# design.net
KiCad netlist of a schematic drawn in Altium Designer
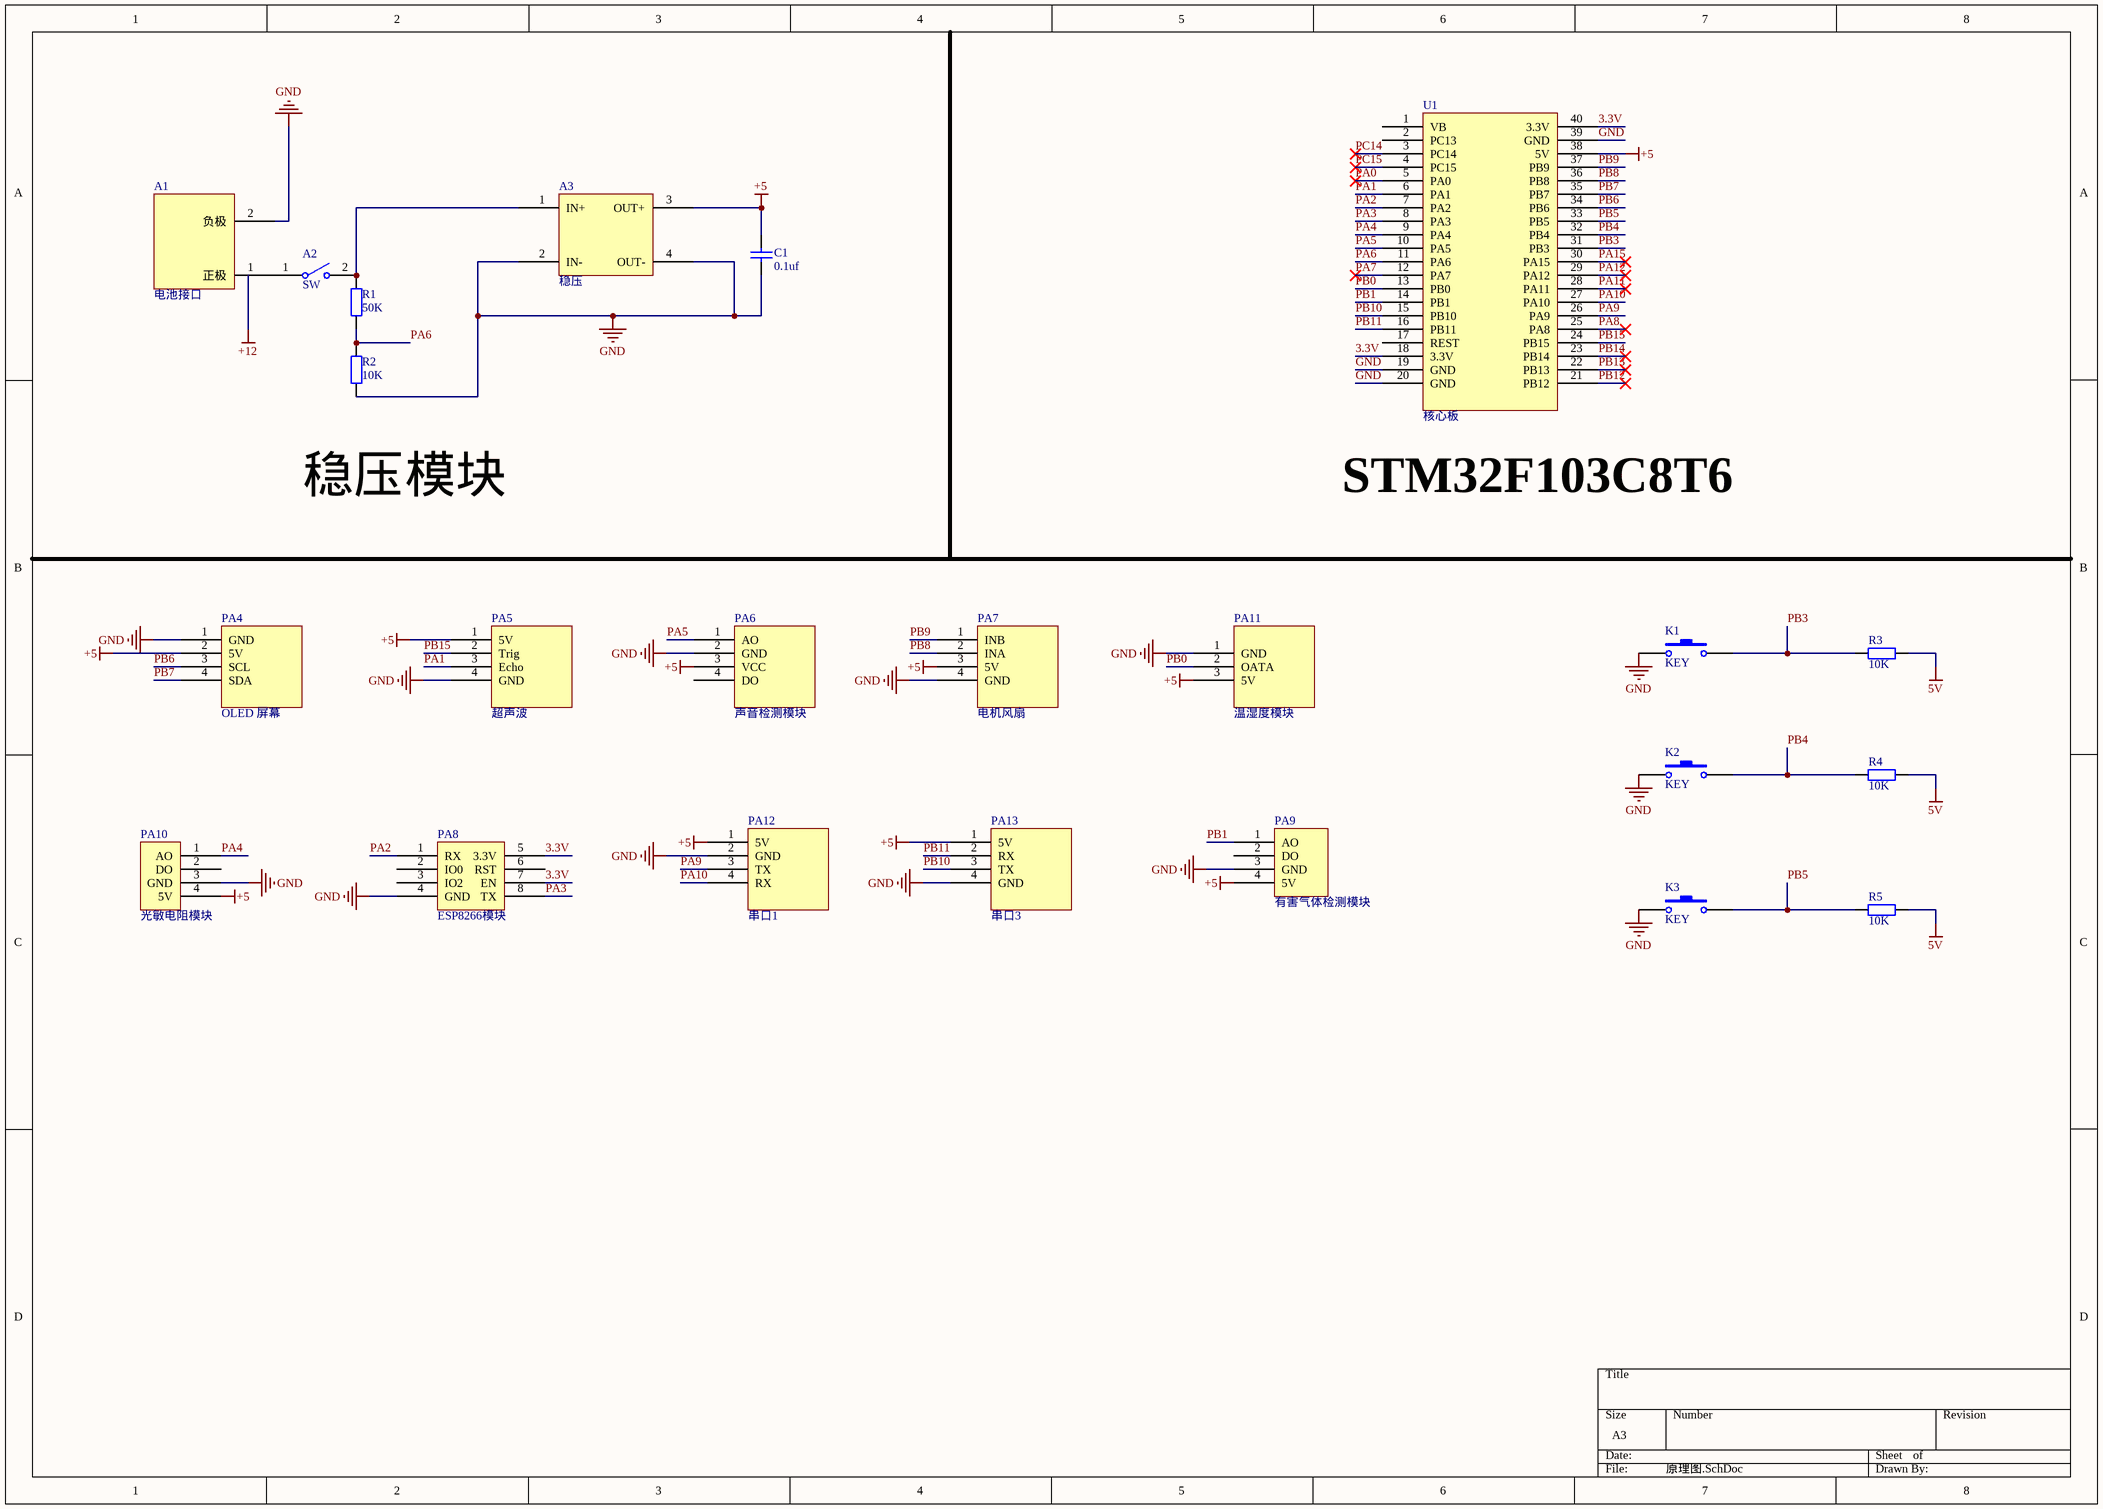
[diagram p0: 原理图.SchDoc]

(export (version "E")
  (design (tool "Eeschema 10.0.6"))
  (components
    (comp (ref "A1") (value "电池接口") (footprint "电池接口") (libsource (lib "原理图元件库") (part "电池接口")))
    (comp (ref "A2") (value "SW") (footprint "开关6脚") (libsource (lib "zjx20180507") (part "SW")))
    (comp (ref "A3") (value "稳压") (footprint "lm2596") (libsource (lib "原理图元件库") (part "稳压")))
    (comp (ref "C1") (value "0.1uf") (footprint "电容") (libsource (lib "张俊翔123456") (part "CAP0.1")))
    (comp (ref "K1") (value "KEY") (footprint "按键2脚") (libsource (lib "zjx20180507") (part "KEY0.2")))
    (comp (ref "K2") (value "KEY") (footprint "按键2脚") (libsource (lib "zjx20180507") (part "KEY0.2")))
    (comp (ref "K3") (value "KEY") (footprint "按键2脚") (libsource (lib "zjx20180507") (part "KEY0.2")))
    (comp (ref "PA4") (value "OLED 屏幕") (footprint "OLED") (libsource (lib "原理图元件库") (part "OLED 屏幕")))
    (comp (ref "PA5") (value "超声波") (footprint "超声波") (libsource (lib "原理图元件库") (part "超声波")))
    (comp (ref "PA6") (value "声音检测模块") (footprint "声音检测模块") (libsource (lib "原理图元件库") (part "声音检测模块")))
    (comp (ref "PA7") (value "电机风扇") (footprint "电机") (libsource (lib "原理图元件库") (part "电机风扇")))
    (comp (ref "PA8") (value "ESP8266模块") (footprint "ESP8266") (libsource (lib "原理图元件库") (part "ESP8266模块")))
    (comp (ref "PA9") (value "有害气体检测模块") (footprint "有害气体检测模块") (libsource (lib "原理图元件库") (part "有害气体检测模块")))
    (comp (ref "PA10") (value "光敏电阻模块") (footprint "光敏电阻") (libsource (lib "原理图元件库") (part "光敏电阻模块")))
    (comp (ref "PA11") (value "温湿度模块") (footprint "温湿度检测模块") (libsource (lib "原理图元件库") (part "温湿度模块")))
    (comp (ref "PA12") (value "串口1") (footprint "串口1") (libsource (lib "原理图元件库") (part "串口1")))
    (comp (ref "PA13") (value "串口3") (footprint "串口3") (libsource (lib "原理图元件库") (part "串口3")))
    (comp (ref "R1") (value "50K") (footprint "电阻") (libsource (lib "") (part "RES0.3_1")))
    (comp (ref "R2") (value "10K") (footprint "电阻") (libsource (lib "") (part "RES0.3_1")))
    (comp (ref "R3") (value "10K") (footprint "电阻") (libsource (lib "zjx20180507") (part "RES0.3")))
    (comp (ref "R4") (value "10K") (footprint "电阻") (libsource (lib "zjx20180507") (part "RES0.3")))
    (comp (ref "R5") (value "10K") (footprint "电阻") (libsource (lib "zjx20180507") (part "RES0.3")))
    (comp (ref "U1") (value "核心板") (footprint "stm32f103c8t6") (libsource (lib "原理图元件库") (part "核心板")))
  )
  (nets
    (net (code "1") (name "+5") (class "Default")
      (node (ref "A3") (pin "3") (pinfunction "OUT+_3") (pintype "passive"))
      (node (ref "C1") (pin "2") (pinfunction "2_2") (pintype "passive"))
      (node (ref "PA10") (pin "4") (pinfunction "5V_4") (pintype "passive"))
      (node (ref "PA11") (pin "3") (pinfunction "5V_3") (pintype "passive"))
      (node (ref "PA12") (pin "1") (pinfunction "5V_1") (pintype "passive"))
      (node (ref "PA13") (pin "1") (pinfunction "5V_1") (pintype "passive"))
      (node (ref "PA4") (pin "2") (pinfunction "5V_2") (pintype "passive"))
      (node (ref "PA5") (pin "1") (pinfunction "5V_1") (pintype "passive"))
      (node (ref "PA6") (pin "3") (pinfunction "VCC_3") (pintype "passive"))
      (node (ref "PA7") (pin "3") (pinfunction "5V_3") (pintype "passive"))
      (node (ref "PA9") (pin "4") (pinfunction "5V_4") (pintype "passive"))
      (node (ref "U1") (pin "38") (pinfunction "5V_38") (pintype "passive"))
    )
    (net (code "3") (name "/3.3V") (class "Default")
      (node (ref "PA8") (pin "5") (pinfunction "3.3V_5") (pintype "passive"))
      (node (ref "PA8") (pin "7") (pinfunction "EN_7") (pintype "passive"))
      (node (ref "U1") (pin "18") (pinfunction "3.3V_18") (pintype "passive"))
      (node (ref "U1") (pin "40") (pinfunction "3.3V_40") (pintype "passive"))
    )
    (net (code "4") (name "/PA0") (class "Default")
      (node (ref "U1") (pin "5") (pinfunction "PA0_5") (pintype "passive+no_connect"))
    )
    (net (code "5") (name "/PA1") (class "Default")
      (node (ref "PA5") (pin "3") (pinfunction "Echo_3") (pintype "passive"))
      (node (ref "U1") (pin "6") (pinfunction "PA1_6") (pintype "passive"))
    )
    (net (code "6") (name "/PA2") (class "Default")
      (node (ref "PA8") (pin "1") (pinfunction "RX_1") (pintype "passive"))
      (node (ref "U1") (pin "7") (pinfunction "PA2_7") (pintype "passive"))
    )
    (net (code "7") (name "/PA3") (class "Default")
      (node (ref "PA8") (pin "8") (pinfunction "TX_8") (pintype "passive"))
      (node (ref "U1") (pin "8") (pinfunction "PA3_8") (pintype "passive"))
    )
    (net (code "8") (name "/PA4") (class "Default")
      (node (ref "PA10") (pin "1") (pinfunction "AO_1") (pintype "passive"))
      (node (ref "U1") (pin "9") (pinfunction "PA4_9") (pintype "passive"))
    )
    (net (code "9") (name "/PA5") (class "Default")
      (node (ref "PA6") (pin "1") (pinfunction "AO_1") (pintype "passive"))
      (node (ref "U1") (pin "10") (pinfunction "PA5_10") (pintype "passive"))
    )
    (net (code "10") (name "/PA6") (class "Default")
      (node (ref "R1") (pin "2") (pinfunction "2_2") (pintype "passive"))
      (node (ref "R2") (pin "1") (pinfunction "1_1") (pintype "passive"))
      (node (ref "U1") (pin "11") (pinfunction "PA6_11") (pintype "passive"))
    )
    (net (code "11") (name "/PA7") (class "Default")
      (node (ref "U1") (pin "12") (pinfunction "PA7_12") (pintype "passive+no_connect"))
    )
    (net (code "12") (name "/PA8") (class "Default")
      (node (ref "U1") (pin "25") (pinfunction "PA8_25") (pintype "passive+no_connect"))
    )
    (net (code "13") (name "/PA9") (class "Default")
      (node (ref "PA12") (pin "3") (pinfunction "TX_3") (pintype "passive"))
      (node (ref "U1") (pin "26") (pinfunction "PA9_26") (pintype "passive"))
    )
    (net (code "14") (name "/PA10") (class "Default")
      (node (ref "PA12") (pin "4") (pinfunction "RX_4") (pintype "passive"))
      (node (ref "U1") (pin "27") (pinfunction "PA10_27") (pintype "passive"))
    )
    (net (code "15") (name "/PA11") (class "Default")
      (node (ref "U1") (pin "28") (pinfunction "PA11_28") (pintype "passive+no_connect"))
    )
    (net (code "16") (name "/PA12") (class "Default")
      (node (ref "U1") (pin "29") (pinfunction "PA12_29") (pintype "passive+no_connect"))
    )
    (net (code "17") (name "/PA15") (class "Default")
      (node (ref "U1") (pin "30") (pinfunction "PA15_30") (pintype "passive+no_connect"))
    )
    (net (code "18") (name "/PB0") (class "Default")
      (node (ref "PA11") (pin "2") (pinfunction "OATA_2") (pintype "passive"))
      (node (ref "U1") (pin "13") (pinfunction "PB0_13") (pintype "passive"))
    )
    (net (code "19") (name "/PB1") (class "Default")
      (node (ref "PA9") (pin "1") (pinfunction "AO_1") (pintype "passive"))
      (node (ref "U1") (pin "14") (pinfunction "PB1_14") (pintype "passive"))
    )
    (net (code "20") (name "/PB3") (class "Default")
      (node (ref "K1") (pin "2") (pinfunction "2_2") (pintype "passive"))
      (node (ref "R3") (pin "2") (pinfunction "2_2") (pintype "passive"))
      (node (ref "U1") (pin "31") (pinfunction "PB3_31") (pintype "passive"))
    )
    (net (code "21") (name "/PB4") (class "Default")
      (node (ref "K2") (pin "2") (pinfunction "2_2") (pintype "passive"))
      (node (ref "R4") (pin "2") (pinfunction "2_2") (pintype "passive"))
      (node (ref "U1") (pin "32") (pinfunction "PB4_32") (pintype "passive"))
    )
    (net (code "22") (name "/PB5") (class "Default")
      (node (ref "K3") (pin "2") (pinfunction "2_2") (pintype "passive"))
      (node (ref "R5") (pin "2") (pinfunction "2_2") (pintype "passive"))
      (node (ref "U1") (pin "33") (pinfunction "PB5_33") (pintype "passive"))
    )
    (net (code "23") (name "/PB6") (class "Default")
      (node (ref "PA4") (pin "3") (pinfunction "SCL_3") (pintype "passive"))
      (node (ref "U1") (pin "34") (pinfunction "PB6_34") (pintype "passive"))
    )
    (net (code "24") (name "/PB7") (class "Default")
      (node (ref "PA4") (pin "4") (pinfunction "SDA_4") (pintype "passive"))
      (node (ref "U1") (pin "35") (pinfunction "PB7_35") (pintype "passive"))
    )
    (net (code "25") (name "/PB8") (class "Default")
      (node (ref "PA7") (pin "2") (pinfunction "INA_2") (pintype "passive"))
      (node (ref "U1") (pin "36") (pinfunction "PB8_36") (pintype "passive"))
    )
    (net (code "26") (name "/PB9") (class "Default")
      (node (ref "PA7") (pin "1") (pinfunction "INB_1") (pintype "passive"))
      (node (ref "U1") (pin "37") (pinfunction "PB9_37") (pintype "passive"))
    )
    (net (code "27") (name "/PB10") (class "Default")
      (node (ref "PA13") (pin "3") (pinfunction "TX_3") (pintype "passive"))
      (node (ref "U1") (pin "15") (pinfunction "PB10_15") (pintype "passive"))
    )
    (net (code "28") (name "/PB11") (class "Default")
      (node (ref "PA13") (pin "2") (pinfunction "RX_2") (pintype "passive"))
      (node (ref "U1") (pin "16") (pinfunction "PB11_16") (pintype "passive"))
    )
    (net (code "29") (name "/PB12") (class "Default")
      (node (ref "U1") (pin "21") (pinfunction "PB12_21") (pintype "passive+no_connect"))
    )
    (net (code "30") (name "/PB13") (class "Default")
      (node (ref "U1") (pin "22") (pinfunction "PB13_22") (pintype "passive+no_connect"))
    )
    (net (code "31") (name "/PB14") (class "Default")
      (node (ref "U1") (pin "23") (pinfunction "PB14_23") (pintype "passive+no_connect"))
    )
    (net (code "32") (name "/PB15") (class "Default")
      (node (ref "PA5") (pin "2") (pinfunction "Trig_2") (pintype "passive"))
      (node (ref "U1") (pin "24") (pinfunction "PB15_24") (pintype "passive"))
    )
    (net (code "33") (name "/PC14") (class "Default")
      (node (ref "U1") (pin "3") (pinfunction "PC14_3") (pintype "passive+no_connect"))
    )
    (net (code "34") (name "/PC15") (class "Default")
      (node (ref "U1") (pin "4") (pinfunction "PC15_4") (pintype "passive+no_connect"))
    )
    (net (code "37") (name "5V") (class "Default")
      (node (ref "R3") (pin "1") (pinfunction "1_1") (pintype "passive"))
      (node (ref "R4") (pin "1") (pinfunction "1_1") (pintype "passive"))
      (node (ref "R5") (pin "1") (pinfunction "1_1") (pintype "passive"))
    )
    (net (code "38") (name "GND") (class "Default")
      (node (ref "A1") (pin "2") (pinfunction "负极_2") (pintype "passive"))
      (node (ref "A3") (pin "2") (pinfunction "IN-_2") (pintype "passive"))
      (node (ref "A3") (pin "4") (pinfunction "OUT-_4") (pintype "passive"))
      (node (ref "C1") (pin "1") (pinfunction "1_1") (pintype "passive"))
      (node (ref "K1") (pin "1") (pinfunction "1_1") (pintype "passive"))
      (node (ref "K2") (pin "1") (pinfunction "1_1") (pintype "passive"))
      (node (ref "K3") (pin "1") (pinfunction "1_1") (pintype "passive"))
      (node (ref "PA10") (pin "3") (pinfunction "GND_3") (pintype "passive"))
      (node (ref "PA11") (pin "1") (pinfunction "GND_1") (pintype "passive"))
      (node (ref "PA12") (pin "2") (pinfunction "GND_2") (pintype "passive"))
      (node (ref "PA13") (pin "4") (pinfunction "GND_4") (pintype "passive"))
      (node (ref "PA4") (pin "1") (pinfunction "GND_1") (pintype "passive"))
      (node (ref "PA5") (pin "4") (pinfunction "GND_4") (pintype "passive"))
      (node (ref "PA6") (pin "2") (pinfunction "GND_2") (pintype "passive"))
      (node (ref "PA7") (pin "4") (pinfunction "GND_4") (pintype "passive"))
      (node (ref "PA8") (pin "4") (pinfunction "GND_4") (pintype "passive"))
      (node (ref "PA9") (pin "3") (pinfunction "GND_3") (pintype "passive"))
      (node (ref "R2") (pin "2") (pinfunction "2_2") (pintype "passive"))
      (node (ref "U1") (pin "19") (pinfunction "GND_19") (pintype "passive"))
      (node (ref "U1") (pin "20") (pinfunction "GND_20") (pintype "passive"))
      (node (ref "U1") (pin "39") (pinfunction "GND_39") (pintype "passive"))
    )
    (net (code "39") (name "Net-(A1-正极)") (class "Default")
      (node (ref "A1") (pin "1") (pinfunction "正极_1") (pintype "passive"))
      (node (ref "A2") (pin "1") (pinfunction "COMMON_1") (pintype "passive"))
    )
    (net (code "40") (name "Net-(A2-NO)") (class "Default")
      (node (ref "A2") (pin "2") (pinfunction "NO_2") (pintype "passive"))
      (node (ref "A3") (pin "1") (pinfunction "IN+_1") (pintype "passive"))
      (node (ref "R1") (pin "1") (pinfunction "1_1") (pintype "passive"))
    )
    (net (code "41") (name "unconnected-(PA6-DO-Pad4)") (class "Default")
      (node (ref "PA6") (pin "4") (pinfunction "DO_4") (pintype "passive"))
    )
    (net (code "42") (name "unconnected-(PA8-IO0-Pad2)") (class "Default")
      (node (ref "PA8") (pin "2") (pinfunction "IO0_2") (pintype "passive"))
    )
    (net (code "43") (name "unconnected-(PA8-IO2-Pad3)") (class "Default")
      (node (ref "PA8") (pin "3") (pinfunction "IO2_3") (pintype "passive"))
    )
    (net (code "44") (name "unconnected-(PA8-RST-Pad6)") (class "Default")
      (node (ref "PA8") (pin "6") (pinfunction "RST_6") (pintype "passive"))
    )
    (net (code "45") (name "unconnected-(PA9-DO-Pad2)") (class "Default")
      (node (ref "PA9") (pin "2") (pinfunction "DO_2") (pintype "passive"))
    )
    (net (code "46") (name "unconnected-(PA10-DO-Pad2)") (class "Default")
      (node (ref "PA10") (pin "2") (pinfunction "DO_2") (pintype "passive"))
    )
    (net (code "47") (name "unconnected-(U1-PC13-Pad2)") (class "Default")
      (node (ref "U1") (pin "2") (pinfunction "PC13_2") (pintype "passive"))
    )
    (net (code "48") (name "unconnected-(U1-REST-Pad17)") (class "Default")
      (node (ref "U1") (pin "17") (pinfunction "REST_17") (pintype "passive"))
    )
    (net (code "49") (name "unconnected-(U1-VB-Pad1)") (class "Default")
      (node (ref "U1") (pin "1") (pinfunction "VB_1") (pintype "passive"))
    )
  )
)
